# wisp-5-peripherals.net
KiCad netlist of a schematic drawn in Altium Designer
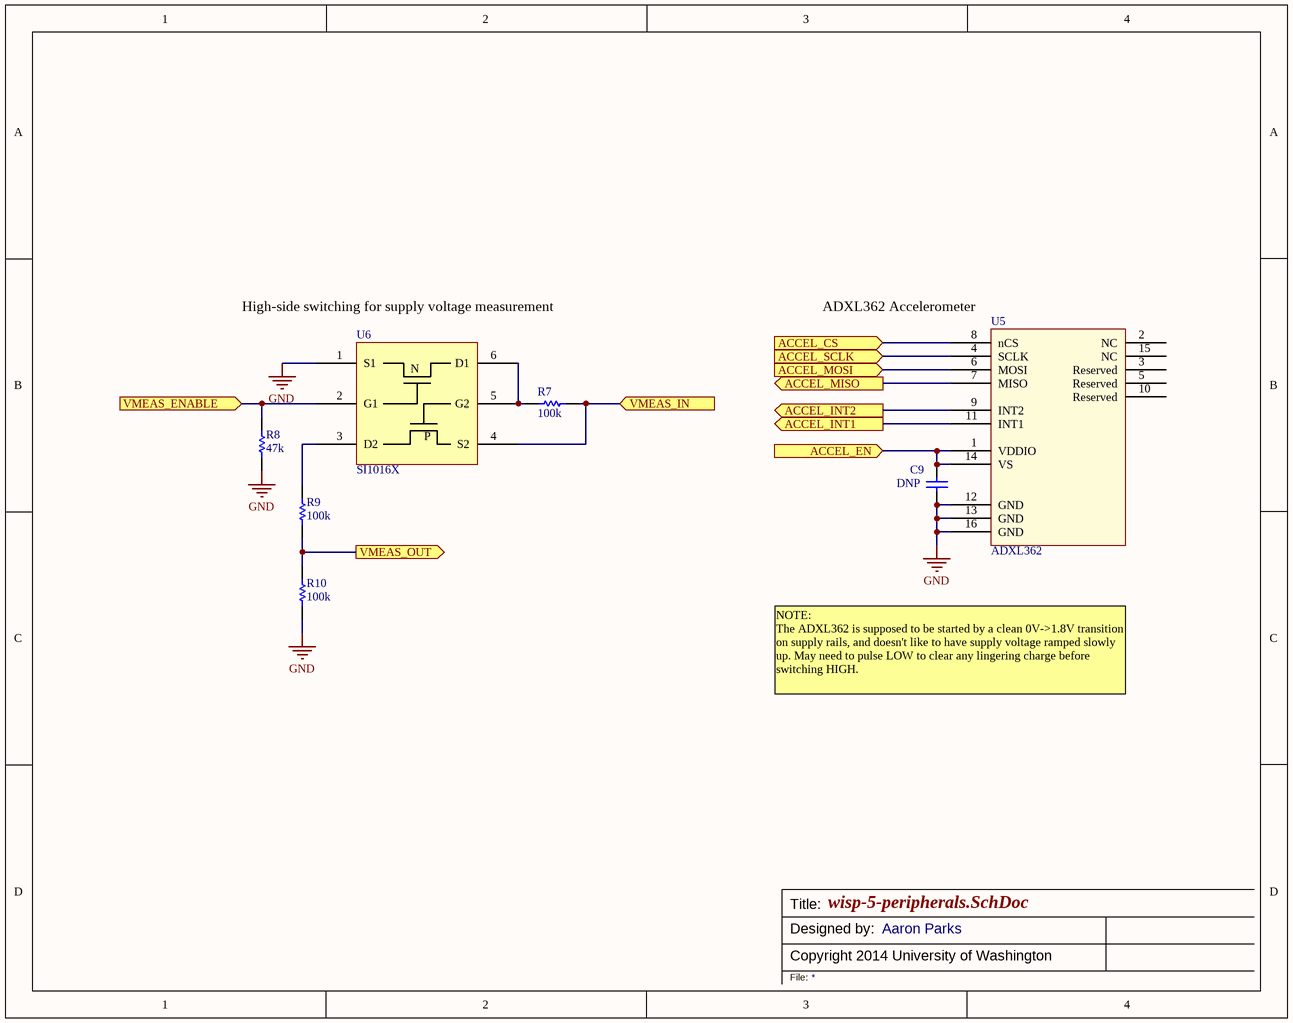
[diagram p0: wisp-5-peripherals.SchDoc]

(export (version "E")
  (design (tool "Eeschema 10.0.6"))
  (components
    (comp (ref "C9")
      (value "Cap")
      (footprint "0402")
      (description "Ceramic Capacitor (Surface Mount)")
      (fields (field (name "DNP") "DNP"))
      (libsource (lib "WISP_AD10") (part "Cap"))
    )
    (comp (ref "R7")
      (value "100k")
      (footprint "0402")
      (description "Chip Resistor (Surface Mount)")
      (fields
        (field (name "MANUFACTURER") "Panasonic")
        (field (name "MANUFACTURER PART NUMBER") "ERJ-2RKF1003X")
      )
      (libsource (lib "WISP_AD10") (part "Res"))
    )
    (comp (ref "R8")
      (value "47k")
      (footprint "0402")
      (description "Chip Resistor (Surface Mount)")
      (fields
        (field (name "MANUFACTURER") "Panasonic")
        (field (name "MANUFACTURER PART NUMBER") "ERJ-2RKF4702X")
      )
      (libsource (lib "WISP_AD10") (part "Res"))
    )
    (comp (ref "R9")
      (value "100k")
      (footprint "0402")
      (description "Chip Resistor (Surface Mount)")
      (fields
        (field (name "MANUFACTURER") "Panasonic")
        (field (name "MANUFACTURER PART NUMBER") "ERJ-2RKF1003X")
      )
      (libsource (lib "WISP_AD10") (part "Res"))
    )
    (comp (ref "R10")
      (value "100k")
      (footprint "0402")
      (description "Chip Resistor (Surface Mount)")
      (fields
        (field (name "MANUFACTURER") "Panasonic")
        (field (name "MANUFACTURER PART NUMBER") "ERJ-2RKF1003X")
      )
      (libsource (lib "WISP_AD10") (part "Res"))
    )
    (comp (ref "U5")
      (value "ADXL362")
      (footprint "ADXL362")
      (description "Analog Devices low power accelerometer")
      (fields
        (field (name "DIGI-KEY PART NUMBER") "ADXL362BCCZ-RL7CT-ND")
        (field (name "MANUFACTURER PART NUMBER") "ADXL362BCCZ-RL7")
      )
      (libsource (lib "WISP_AD10") (part "ADXL362"))
    )
    (comp (ref "U6")
      (value "SI1016X")
      (footprint "SC-89-6 Vishay")
      (description "NMOS and PMOS array")
      (fields
        (field (name "DIGI-KEY PART NUMBER") "SI1016X-T1-GE3CT-ND")
        (field (name "MANUFACTURER PART NUMBER") "SI1016X-T1-GE3")
      )
      (libsource (lib "WISP_AD10") (part "SI1016X"))
    )
  )
  (nets
    (net (code "1") (name "/ACCEL_CS") (class "Default")
      (node (ref "U5") (pin "8") (pinfunction "nCS_8") (pintype "passive"))
    )
    (net (code "2") (name "/ACCEL_EN") (class "Default")
      (node (ref "C9") (pin "2") (pinfunction "2_2") (pintype "passive"))
      (node (ref "U5") (pin "1") (pinfunction "VDDIO_1") (pintype "passive"))
      (node (ref "U5") (pin "14") (pinfunction "VS_14") (pintype "passive"))
    )
    (net (code "3") (name "/ACCEL_INT1") (class "Default")
      (node (ref "U5") (pin "11") (pinfunction "INT1_11") (pintype "passive"))
    )
    (net (code "4") (name "/ACCEL_INT2") (class "Default")
      (node (ref "U5") (pin "9") (pinfunction "INT2_9") (pintype "passive"))
    )
    (net (code "5") (name "/ACCEL_MISO") (class "Default")
      (node (ref "U5") (pin "7") (pinfunction "MISO_7") (pintype "passive"))
    )
    (net (code "6") (name "/ACCEL_MOSI") (class "Default")
      (node (ref "U5") (pin "6") (pinfunction "MOSI_6") (pintype "passive"))
    )
    (net (code "7") (name "/ACCEL_SCLK") (class "Default")
      (node (ref "U5") (pin "4") (pinfunction "SCLK_4") (pintype "passive"))
    )
    (net (code "8") (name "/VMEAS_ENABLE") (class "Default")
      (node (ref "R8") (pin "2") (pinfunction "2_2") (pintype "passive"))
      (node (ref "U6") (pin "2") (pinfunction "G1_2") (pintype "passive"))
    )
    (net (code "9") (name "/VMEAS_IN") (class "Default")
      (node (ref "R7") (pin "1") (pinfunction "1_1") (pintype "passive"))
      (node (ref "U6") (pin "4") (pinfunction "S2_4") (pintype "passive"))
    )
    (net (code "10") (name "/VMEAS_OUT") (class "Default")
      (node (ref "R10") (pin "2") (pinfunction "2_2") (pintype "passive"))
      (node (ref "R9") (pin "1") (pinfunction "1_1") (pintype "passive"))
    )
    (net (code "11") (name "GND") (class "Default")
      (node (ref "C9") (pin "1") (pinfunction "1_1") (pintype "passive"))
      (node (ref "R10") (pin "1") (pinfunction "1_1") (pintype "passive"))
      (node (ref "R8") (pin "1") (pinfunction "1_1") (pintype "passive"))
      (node (ref "U5") (pin "12") (pinfunction "GND_12") (pintype "passive"))
      (node (ref "U5") (pin "13") (pinfunction "GND_13") (pintype "passive"))
      (node (ref "U5") (pin "16") (pinfunction "GND_16") (pintype "passive"))
      (node (ref "U6") (pin "1") (pinfunction "S1_1") (pintype "passive"))
    )
    (net (code "12") (name "Net-(U6-D1)") (class "Default")
      (node (ref "R7") (pin "2") (pinfunction "2_2") (pintype "passive"))
      (node (ref "U6") (pin "5") (pinfunction "G2_5") (pintype "passive"))
      (node (ref "U6") (pin "6") (pinfunction "D1_6") (pintype "passive"))
    )
    (net (code "13") (name "Net-(U6-D2)") (class "Default")
      (node (ref "R9") (pin "2") (pinfunction "2_2") (pintype "passive"))
      (node (ref "U6") (pin "3") (pinfunction "D2_3") (pintype "passive"))
    )
    (net (code "14") (name "unconnected-(U5-NC-Pad2)") (class "Default")
      (node (ref "U5") (pin "2") (pinfunction "NC_2") (pintype "passive"))
    )
    (net (code "15") (name "unconnected-(U5-NC-Pad15)") (class "Default")
      (node (ref "U5") (pin "15") (pinfunction "NC_15") (pintype "passive"))
    )
    (net (code "16") (name "unconnected-(U5-Reserved-Pad3)") (class "Default")
      (node (ref "U5") (pin "3") (pinfunction "Reserved_3") (pintype "passive"))
    )
    (net (code "17") (name "unconnected-(U5-Reserved-Pad5)") (class "Default")
      (node (ref "U5") (pin "5") (pinfunction "Reserved_5") (pintype "passive"))
    )
    (net (code "18") (name "unconnected-(U5-Reserved-Pad10)") (class "Default")
      (node (ref "U5") (pin "10") (pinfunction "Reserved_10") (pintype "passive"))
    )
  )
)
